# Orbiter_V3_2.net
KiCad netlist of a schematic drawn in EAGLE
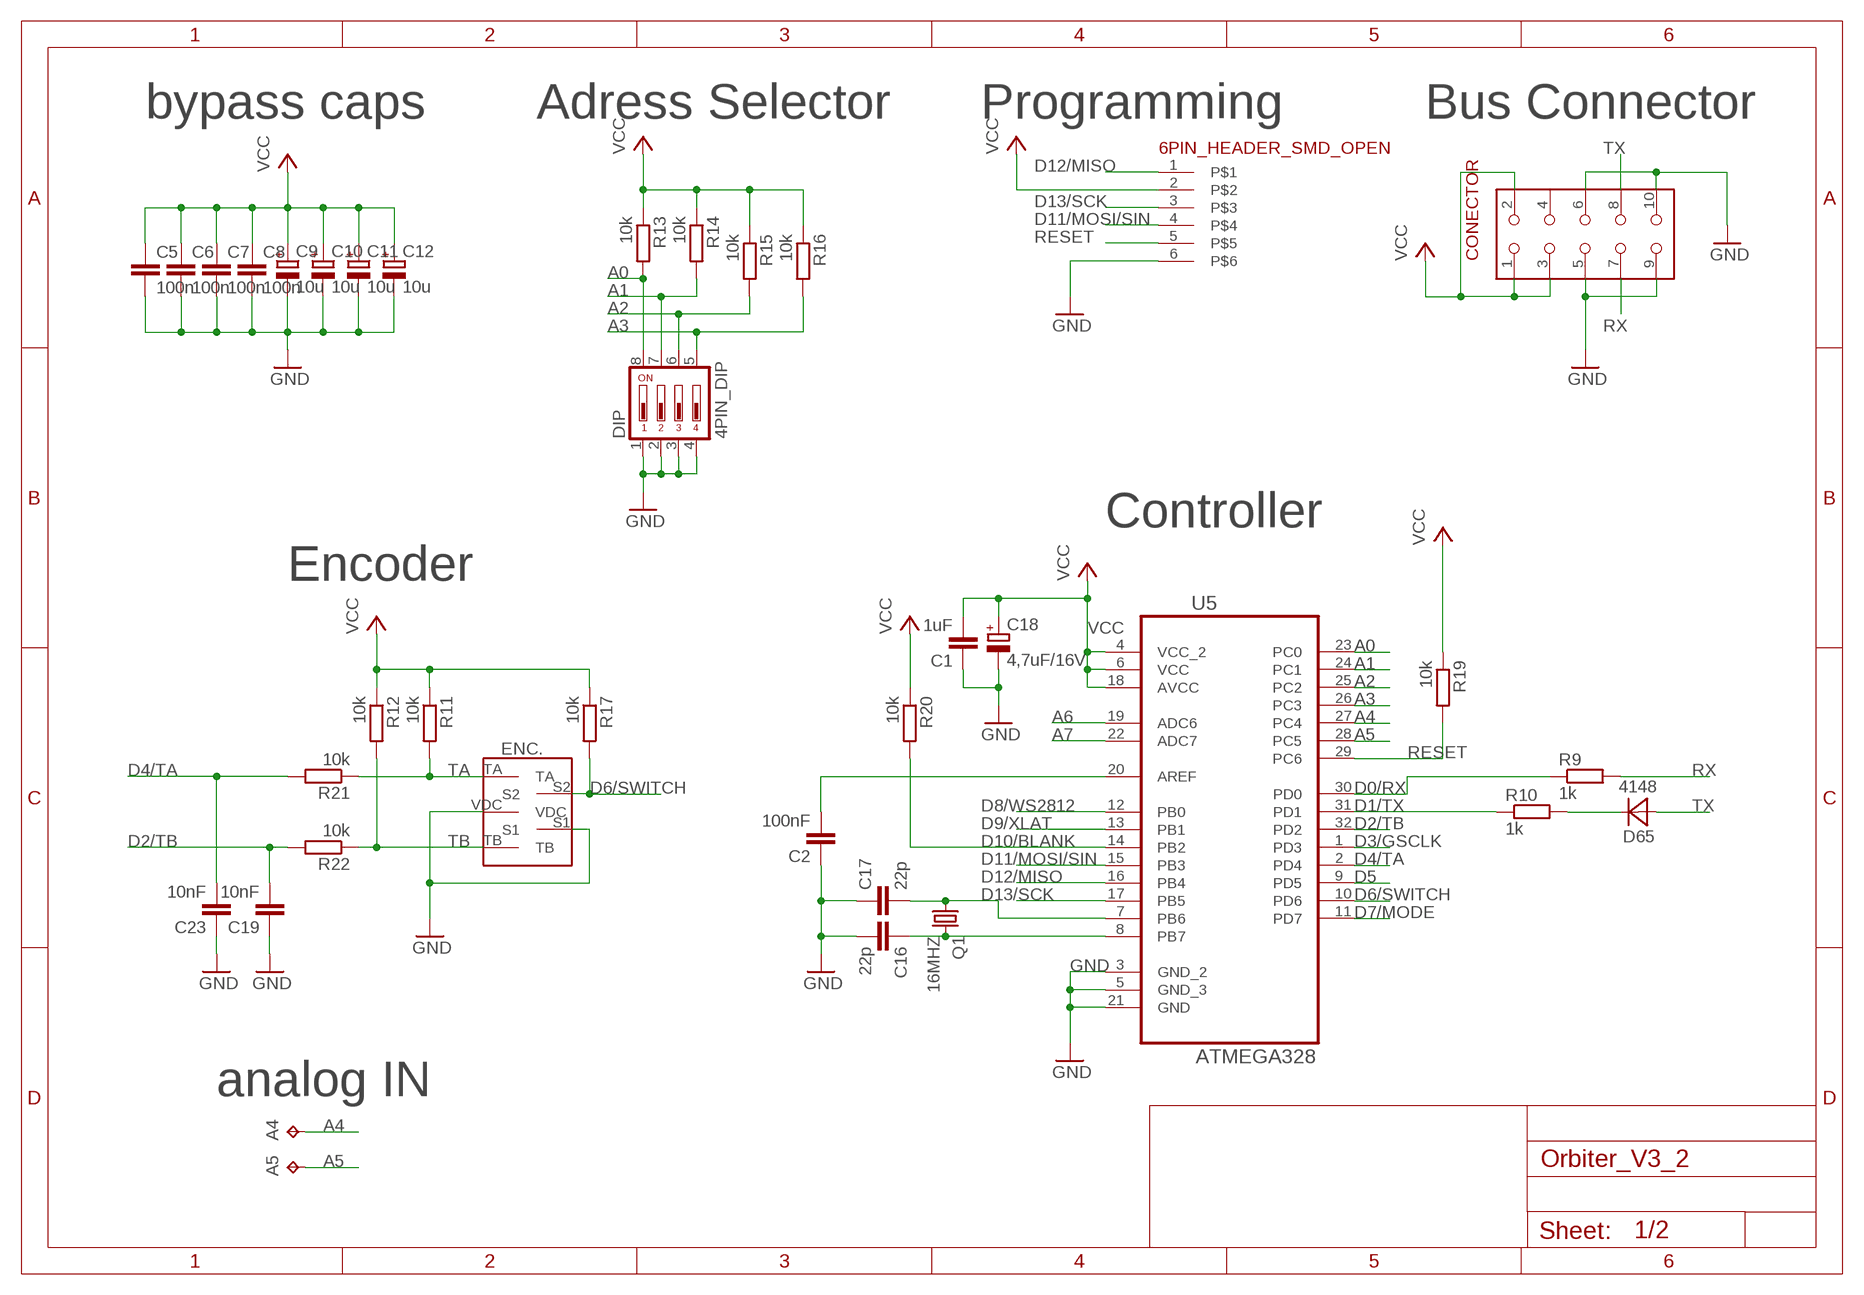
[diagram p0: schematic, sheet 1]
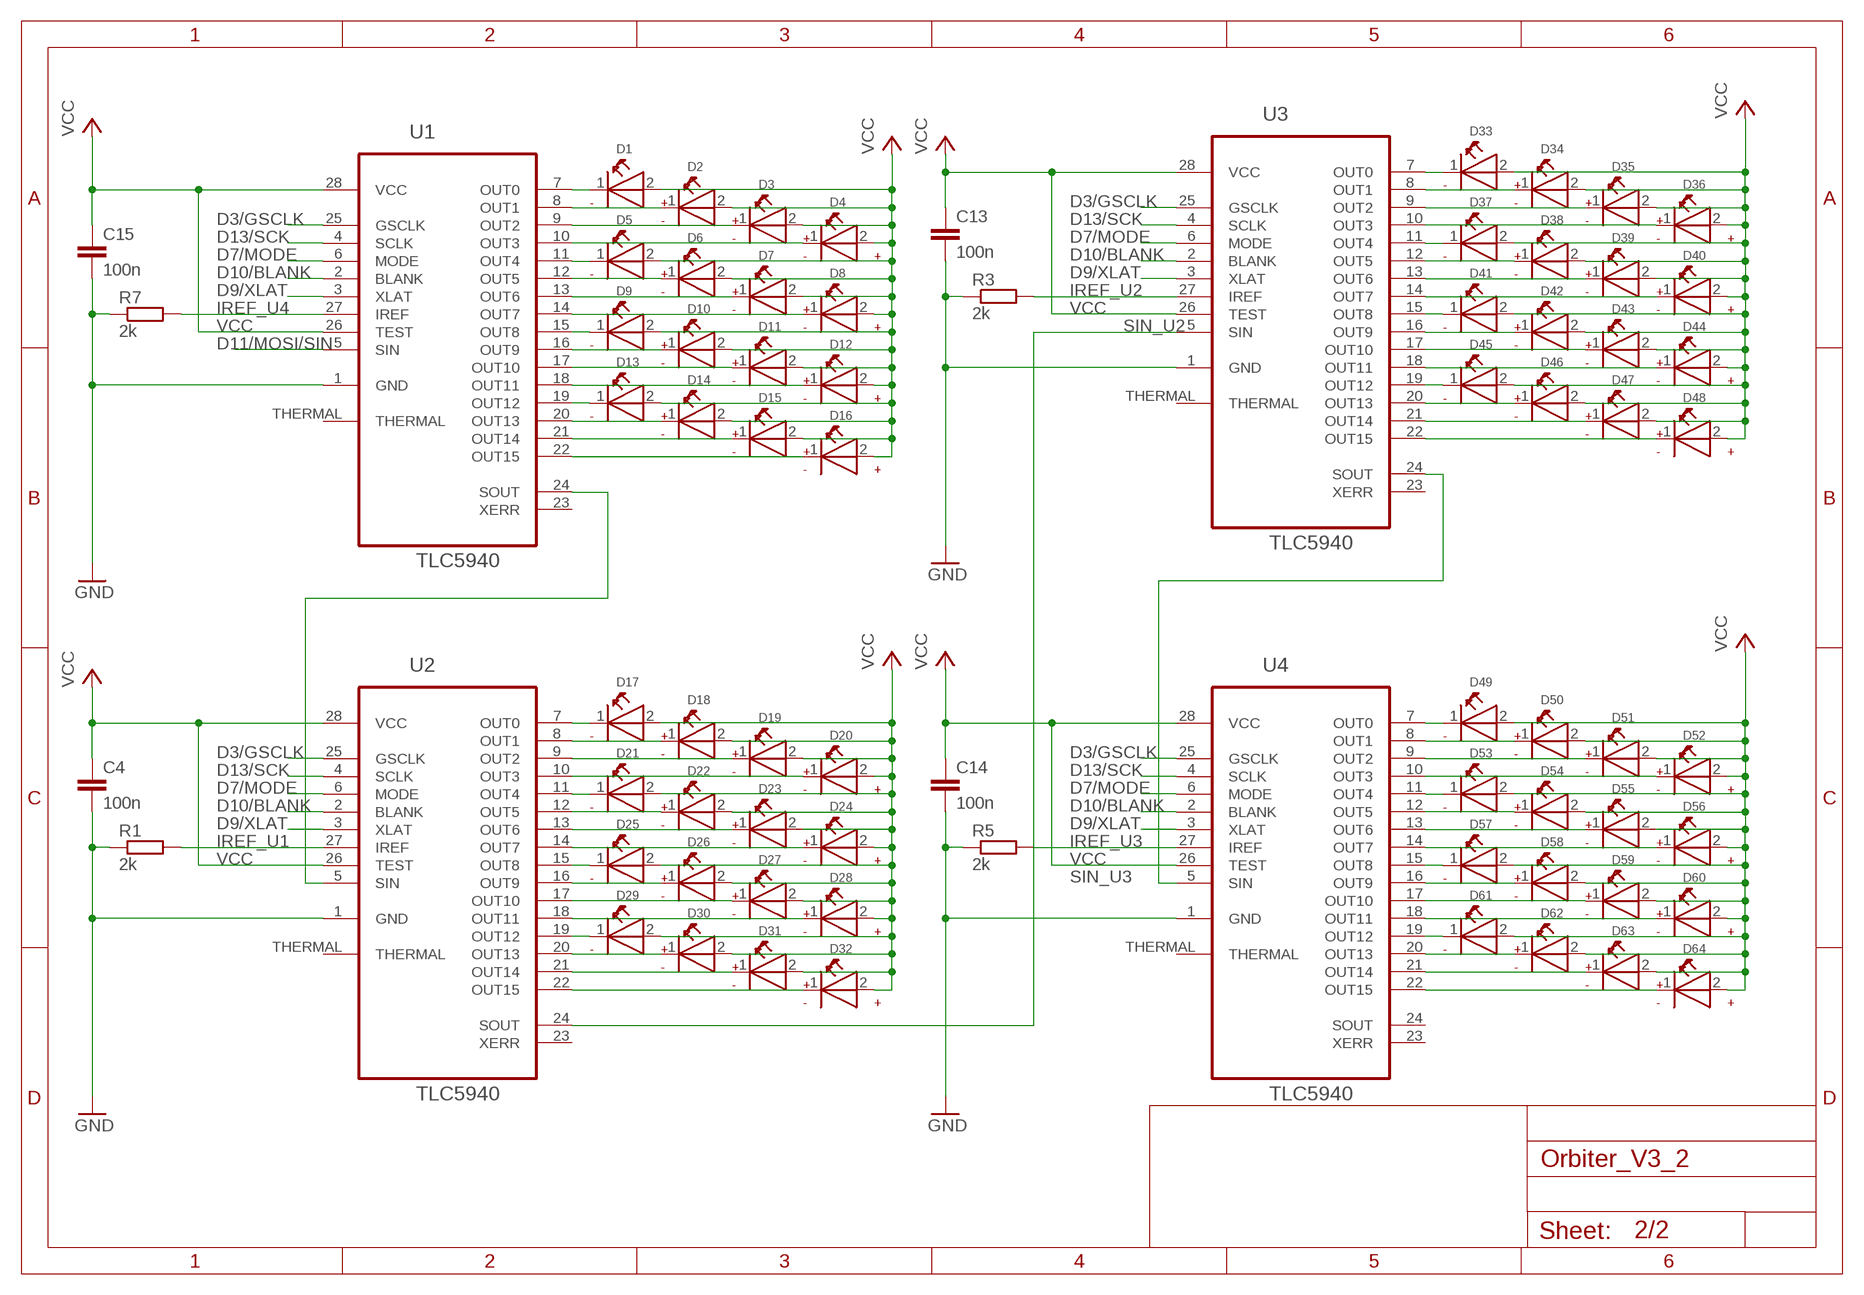
[diagram p1: schematic, sheet 2]

(export (version "E")
  (design (tool "Eeschema 10.0.6"))
  (components
    (comp (ref "A4")
      (value "TPSMD")
      (footprint "eagle-import:TP")
      (libsource (lib "eagle-import") (part "TPSMD"))
    )
    (comp (ref "A5")
      (value "TPSMD")
      (footprint "eagle-import:TP")
      (libsource (lib "eagle-import") (part "TPSMD"))
    )
    (comp (ref "C1")
      (value "1uF")
      (footprint "eagle-import:C0603")
      (libsource (lib "eagle-import") (part "CAPACITOR{dblquote}"))
    )
    (comp (ref "C2")
      (value "100nF")
      (footprint "eagle-import:C0603")
      (libsource (lib "eagle-import") (part "CAPACITOR{dblquote}"))
    )
    (comp (ref "C5")
      (value "100n")
      (footprint "eagle-import:C0603")
      (libsource (lib "eagle-import") (part "CAPACITOR{dblquote}"))
    )
    (comp (ref "C6")
      (value "100n")
      (footprint "eagle-import:C0603")
      (libsource (lib "eagle-import") (part "CAPACITOR{dblquote}"))
    )
    (comp (ref "C7")
      (value "100n")
      (footprint "eagle-import:C0603")
      (libsource (lib "eagle-import") (part "CAPACITOR{dblquote}"))
    )
    (comp (ref "C8")
      (value "100n")
      (footprint "eagle-import:C0603")
      (libsource (lib "eagle-import") (part "CAPACITOR{dblquote}"))
    )
    (comp (ref "C9")
      (value "10u")
      (footprint "eagle-import:153CLV-0605")
      (libsource (lib "eagle-import") (part "SMD_ELCTROLYTIC"))
    )
    (comp (ref "C10")
      (value "10u")
      (footprint "eagle-import:153CLV-0605")
      (libsource (lib "eagle-import") (part "SMD_ELCTROLYTIC"))
    )
    (comp (ref "C11")
      (value "10u")
      (footprint "eagle-import:153CLV-0605")
      (libsource (lib "eagle-import") (part "SMD_ELCTROLYTIC"))
    )
    (comp (ref "C12")
      (value "10u")
      (footprint "eagle-import:153CLV-0605")
      (libsource (lib "eagle-import") (part "SMD_ELCTROLYTIC"))
    )
    (comp (ref "C16")
      (value "22p")
      (footprint "eagle-import:C0603")
      (libsource (lib "eagle-import") (part "CAPACITOR{dblquote}"))
    )
    (comp (ref "C17")
      (value "22p")
      (footprint "eagle-import:C0603")
      (libsource (lib "eagle-import") (part "CAPACITOR{dblquote}"))
    )
    (comp (ref "C18")
      (value "4,7uF/16V")
      (footprint "eagle-import:153CLV-0605")
      (libsource (lib "eagle-import") (part "SMD_ELCTROLYTIC"))
    )
    (comp (ref "C19")
      (value "10nF")
      (footprint "eagle-import:C0603")
      (libsource (lib "eagle-import") (part "CAPACITOR{dblquote}"))
    )
    (comp (ref "C23")
      (value "10nF")
      (footprint "eagle-import:C0603")
      (libsource (lib "eagle-import") (part "CAPACITOR{dblquote}"))
    )
    (comp (ref "CONECTOR")
      (value "10PIN_HEADER_SMD")
      (footprint "eagle-import:87832-10")
      (libsource (lib "eagle-import") (part "10PIN_HEADER_SMD"))
    )
    (comp (ref "D65")
      (value "4148")
      (footprint "eagle-import:SOD323-R")
      (libsource (lib "eagle-import") (part "4148"))
    )
    (comp (ref "DIP")
      (value "4PIN_DIP")
      (footprint "eagle-import:CTS-219-04")
      (libsource (lib "eagle-import") (part "4PIN_DIP"))
    )
    (comp (ref "ENC.")
      (value "BOURNS_ENCODER")
      (footprint "eagle-import:BOURNS_ENCODER_SMD")
      (libsource (lib "eagle-import") (part "BOURNS_ENCODER"))
    )
    (comp (ref "PROG.")
      (value "6PIN_HEADER_SMD_OPEN")
      (footprint "eagle-import:6PIN_HEADER_SMD_OPEN")
      (libsource (lib "eagle-import") (part "6PIN_HEADER_SMD_OPEN"))
    )
    (comp (ref "Q1")
      (value "16MHZ")
      (footprint "eagle-import:SM49")
      (libsource (lib "eagle-import") (part "CRYSTAL_SM49"))
    )
    (comp (ref "R9")
      (value "1k")
      (footprint "eagle-import:R0805")
      (libsource (lib "eagle-import") (part "RESISTOR{dblquote}"))
    )
    (comp (ref "R10")
      (value "1k")
      (footprint "eagle-import:R0805")
      (libsource (lib "eagle-import") (part "RESISTOR{dblquote}"))
    )
    (comp (ref "R11")
      (value "10k")
      (footprint "eagle-import:R0805")
      (libsource (lib "eagle-import") (part "RESISTOR{dblquote}"))
    )
    (comp (ref "R12")
      (value "10k")
      (footprint "eagle-import:R0805")
      (libsource (lib "eagle-import") (part "RESISTOR{dblquote}"))
    )
    (comp (ref "R13")
      (value "10k")
      (footprint "eagle-import:R0805")
      (libsource (lib "eagle-import") (part "RESISTOR{dblquote}"))
    )
    (comp (ref "R14")
      (value "10k")
      (footprint "eagle-import:R0805")
      (libsource (lib "eagle-import") (part "RESISTOR{dblquote}"))
    )
    (comp (ref "R15")
      (value "10k")
      (footprint "eagle-import:R0805")
      (libsource (lib "eagle-import") (part "RESISTOR{dblquote}"))
    )
    (comp (ref "R16")
      (value "10k")
      (footprint "eagle-import:R0805")
      (libsource (lib "eagle-import") (part "RESISTOR{dblquote}"))
    )
    (comp (ref "R17")
      (value "10k")
      (footprint "eagle-import:R0805")
      (libsource (lib "eagle-import") (part "RESISTOR{dblquote}"))
    )
    (comp (ref "R19")
      (value "10k")
      (footprint "eagle-import:R0805")
      (libsource (lib "eagle-import") (part "RESISTOR{dblquote}"))
    )
    (comp (ref "R20")
      (value "10k")
      (footprint "eagle-import:R0805")
      (libsource (lib "eagle-import") (part "RESISTOR{dblquote}"))
    )
    (comp (ref "R21")
      (value "10k")
      (footprint "eagle-import:R0805")
      (libsource (lib "eagle-import") (part "RESISTOR{dblquote}"))
    )
    (comp (ref "R22")
      (value "10k")
      (footprint "eagle-import:R0805")
      (libsource (lib "eagle-import") (part "RESISTOR{dblquote}"))
    )
    (comp (ref "U5")
      (value "ATMEGA328")
      (footprint "eagle-import:QFP80P900X900X120-32N")
      (fields (field (name "MPN") "ATMEGA328P-AU"))
      (libsource (lib "eagle-import") (part "ATMEGA328P-AU"))
    )
    (comp (ref "C4")
      (value "100n")
      (footprint "eagle-import:C0603")
      (libsource (lib "eagle-import") (part "CAPACITOR{dblquote}"))
    )
    (comp (ref "C13")
      (value "100n")
      (footprint "eagle-import:C0603")
      (libsource (lib "eagle-import") (part "CAPACITOR{dblquote}"))
    )
    (comp (ref "C14")
      (value "100n")
      (footprint "eagle-import:C0603")
      (libsource (lib "eagle-import") (part "CAPACITOR{dblquote}"))
    )
    (comp (ref "C15")
      (value "100n")
      (footprint "eagle-import:C0603")
      (libsource (lib "eagle-import") (part "CAPACITOR{dblquote}"))
    )
    (comp (ref "D1")
      (value "SMD_LED_0603")
      (footprint "eagle-import:WL-SMCW_0603")
      (libsource (lib "eagle-import") (part "SMD_LED_0603"))
    )
    (comp (ref "D2")
      (value "SMD_LED_0603")
      (footprint "eagle-import:WL-SMCW_0603")
      (libsource (lib "eagle-import") (part "SMD_LED_0603"))
    )
    (comp (ref "D3")
      (value "SMD_LED_0603")
      (footprint "eagle-import:WL-SMCW_0603")
      (libsource (lib "eagle-import") (part "SMD_LED_0603"))
    )
    (comp (ref "D4")
      (value "SMD_LED_0603")
      (footprint "eagle-import:WL-SMCW_0603")
      (libsource (lib "eagle-import") (part "SMD_LED_0603"))
    )
    (comp (ref "D5")
      (value "SMD_LED_0603")
      (footprint "eagle-import:WL-SMCW_0603")
      (libsource (lib "eagle-import") (part "SMD_LED_0603"))
    )
    (comp (ref "D6")
      (value "SMD_LED_0603")
      (footprint "eagle-import:WL-SMCW_0603")
      (libsource (lib "eagle-import") (part "SMD_LED_0603"))
    )
    (comp (ref "D7")
      (value "SMD_LED_0603")
      (footprint "eagle-import:WL-SMCW_0603")
      (libsource (lib "eagle-import") (part "SMD_LED_0603"))
    )
    (comp (ref "D8")
      (value "SMD_LED_0603")
      (footprint "eagle-import:WL-SMCW_0603")
      (libsource (lib "eagle-import") (part "SMD_LED_0603"))
    )
    (comp (ref "D9")
      (value "SMD_LED_0603")
      (footprint "eagle-import:WL-SMCW_0603")
      (libsource (lib "eagle-import") (part "SMD_LED_0603"))
    )
    (comp (ref "D10")
      (value "SMD_LED_0603")
      (footprint "eagle-import:WL-SMCW_0603")
      (libsource (lib "eagle-import") (part "SMD_LED_0603"))
    )
    (comp (ref "D11")
      (value "SMD_LED_0603")
      (footprint "eagle-import:WL-SMCW_0603")
      (libsource (lib "eagle-import") (part "SMD_LED_0603"))
    )
    (comp (ref "D12")
      (value "SMD_LED_0603")
      (footprint "eagle-import:WL-SMCW_0603")
      (libsource (lib "eagle-import") (part "SMD_LED_0603"))
    )
    (comp (ref "D13")
      (value "SMD_LED_0603")
      (footprint "eagle-import:WL-SMCW_0603")
      (libsource (lib "eagle-import") (part "SMD_LED_0603"))
    )
    (comp (ref "D14")
      (value "SMD_LED_0603")
      (footprint "eagle-import:WL-SMCW_0603")
      (libsource (lib "eagle-import") (part "SMD_LED_0603"))
    )
    (comp (ref "D15")
      (value "SMD_LED_0603")
      (footprint "eagle-import:WL-SMCW_0603")
      (libsource (lib "eagle-import") (part "SMD_LED_0603"))
    )
    (comp (ref "D16")
      (value "SMD_LED_0603")
      (footprint "eagle-import:WL-SMCW_0603")
      (libsource (lib "eagle-import") (part "SMD_LED_0603"))
    )
    (comp (ref "D17")
      (value "SMD_LED_0603")
      (footprint "eagle-import:WL-SMCW_0603")
      (libsource (lib "eagle-import") (part "SMD_LED_0603"))
    )
    (comp (ref "D18")
      (value "SMD_LED_0603")
      (footprint "eagle-import:WL-SMCW_0603")
      (libsource (lib "eagle-import") (part "SMD_LED_0603"))
    )
    (comp (ref "D19")
      (value "SMD_LED_0603")
      (footprint "eagle-import:WL-SMCW_0603")
      (libsource (lib "eagle-import") (part "SMD_LED_0603"))
    )
    (comp (ref "D20")
      (value "SMD_LED_0603")
      (footprint "eagle-import:WL-SMCW_0603")
      (libsource (lib "eagle-import") (part "SMD_LED_0603"))
    )
    (comp (ref "D21")
      (value "SMD_LED_0603")
      (footprint "eagle-import:WL-SMCW_0603")
      (libsource (lib "eagle-import") (part "SMD_LED_0603"))
    )
    (comp (ref "D22")
      (value "SMD_LED_0603")
      (footprint "eagle-import:WL-SMCW_0603")
      (libsource (lib "eagle-import") (part "SMD_LED_0603"))
    )
    (comp (ref "D23")
      (value "SMD_LED_0603")
      (footprint "eagle-import:WL-SMCW_0603")
      (libsource (lib "eagle-import") (part "SMD_LED_0603"))
    )
    (comp (ref "D24")
      (value "SMD_LED_0603")
      (footprint "eagle-import:WL-SMCW_0603")
      (libsource (lib "eagle-import") (part "SMD_LED_0603"))
    )
    (comp (ref "D25")
      (value "SMD_LED_0603")
      (footprint "eagle-import:WL-SMCW_0603")
      (libsource (lib "eagle-import") (part "SMD_LED_0603"))
    )
    (comp (ref "D26")
      (value "SMD_LED_0603")
      (footprint "eagle-import:WL-SMCW_0603")
      (libsource (lib "eagle-import") (part "SMD_LED_0603"))
    )
    (comp (ref "D27")
      (value "SMD_LED_0603")
      (footprint "eagle-import:WL-SMCW_0603")
      (libsource (lib "eagle-import") (part "SMD_LED_0603"))
    )
    (comp (ref "D28")
      (value "SMD_LED_0603")
      (footprint "eagle-import:WL-SMCW_0603")
      (libsource (lib "eagle-import") (part "SMD_LED_0603"))
    )
    (comp (ref "D29")
      (value "SMD_LED_0603")
      (footprint "eagle-import:WL-SMCW_0603")
      (libsource (lib "eagle-import") (part "SMD_LED_0603"))
    )
    (comp (ref "D30")
      (value "SMD_LED_0603")
      (footprint "eagle-import:WL-SMCW_0603")
      (libsource (lib "eagle-import") (part "SMD_LED_0603"))
    )
    (comp (ref "D31")
      (value "SMD_LED_0603")
      (footprint "eagle-import:WL-SMCW_0603")
      (libsource (lib "eagle-import") (part "SMD_LED_0603"))
    )
    (comp (ref "D32")
      (value "SMD_LED_0603")
      (footprint "eagle-import:WL-SMCW_0603")
      (libsource (lib "eagle-import") (part "SMD_LED_0603"))
    )
    (comp (ref "D33")
      (value "SMD_LED_0603")
      (footprint "eagle-import:WL-SMCW_0603")
      (libsource (lib "eagle-import") (part "SMD_LED_0603"))
    )
    (comp (ref "D34")
      (value "SMD_LED_0603")
      (footprint "eagle-import:WL-SMCW_0603")
      (libsource (lib "eagle-import") (part "SMD_LED_0603"))
    )
    (comp (ref "D35")
      (value "SMD_LED_0603")
      (footprint "eagle-import:WL-SMCW_0603")
      (libsource (lib "eagle-import") (part "SMD_LED_0603"))
    )
    (comp (ref "D36")
      (value "SMD_LED_0603")
      (footprint "eagle-import:WL-SMCW_0603")
      (libsource (lib "eagle-import") (part "SMD_LED_0603"))
    )
    (comp (ref "D37")
      (value "SMD_LED_0603")
      (footprint "eagle-import:WL-SMCW_0603")
      (libsource (lib "eagle-import") (part "SMD_LED_0603"))
    )
    (comp (ref "D38")
      (value "SMD_LED_0603")
      (footprint "eagle-import:WL-SMCW_0603")
      (libsource (lib "eagle-import") (part "SMD_LED_0603"))
    )
    (comp (ref "D39")
      (value "SMD_LED_0603")
      (footprint "eagle-import:WL-SMCW_0603")
      (libsource (lib "eagle-import") (part "SMD_LED_0603"))
    )
    (comp (ref "D40")
      (value "SMD_LED_0603")
      (footprint "eagle-import:WL-SMCW_0603")
      (libsource (lib "eagle-import") (part "SMD_LED_0603"))
    )
    (comp (ref "D41")
      (value "SMD_LED_0603")
      (footprint "eagle-import:WL-SMCW_0603")
      (libsource (lib "eagle-import") (part "SMD_LED_0603"))
    )
    (comp (ref "D42")
      (value "SMD_LED_0603")
      (footprint "eagle-import:WL-SMCW_0603")
      (libsource (lib "eagle-import") (part "SMD_LED_0603"))
    )
    (comp (ref "D43")
      (value "SMD_LED_0603")
      (footprint "eagle-import:WL-SMCW_0603")
      (libsource (lib "eagle-import") (part "SMD_LED_0603"))
    )
    (comp (ref "D44")
      (value "SMD_LED_0603")
      (footprint "eagle-import:WL-SMCW_0603")
      (libsource (lib "eagle-import") (part "SMD_LED_0603"))
    )
    (comp (ref "D45")
      (value "SMD_LED_0603")
      (footprint "eagle-import:WL-SMCW_0603")
      (libsource (lib "eagle-import") (part "SMD_LED_0603"))
    )
    (comp (ref "D46")
      (value "SMD_LED_0603")
      (footprint "eagle-import:WL-SMCW_0603")
      (libsource (lib "eagle-import") (part "SMD_LED_0603"))
    )
    (comp (ref "D47")
      (value "SMD_LED_0603")
      (footprint "eagle-import:WL-SMCW_0603")
      (libsource (lib "eagle-import") (part "SMD_LED_0603"))
    )
    (comp (ref "D48")
      (value "SMD_LED_0603")
      (footprint "eagle-import:WL-SMCW_0603")
      (libsource (lib "eagle-import") (part "SMD_LED_0603"))
    )
    (comp (ref "D49")
      (value "SMD_LED_0603")
      (footprint "eagle-import:WL-SMCW_0603")
      (libsource (lib "eagle-import") (part "SMD_LED_0603"))
    )
    (comp (ref "D50")
      (value "SMD_LED_0603")
      (footprint "eagle-import:WL-SMCW_0603")
      (libsource (lib "eagle-import") (part "SMD_LED_0603"))
    )
    (comp (ref "D51")
      (value "SMD_LED_0603")
      (footprint "eagle-import:WL-SMCW_0603")
      (libsource (lib "eagle-import") (part "SMD_LED_0603"))
    )
    (comp (ref "D52")
      (value "SMD_LED_0603")
      (footprint "eagle-import:WL-SMCW_0603")
      (libsource (lib "eagle-import") (part "SMD_LED_0603"))
    )
    (comp (ref "D53")
      (value "SMD_LED_0603")
      (footprint "eagle-import:WL-SMCW_0603")
      (libsource (lib "eagle-import") (part "SMD_LED_0603"))
    )
    (comp (ref "D54")
      (value "SMD_LED_0603")
      (footprint "eagle-import:WL-SMCW_0603")
      (libsource (lib "eagle-import") (part "SMD_LED_0603"))
    )
    (comp (ref "D55")
      (value "SMD_LED_0603")
      (footprint "eagle-import:WL-SMCW_0603")
      (libsource (lib "eagle-import") (part "SMD_LED_0603"))
    )
    (comp (ref "D56")
      (value "SMD_LED_0603")
      (footprint "eagle-import:WL-SMCW_0603")
      (libsource (lib "eagle-import") (part "SMD_LED_0603"))
    )
    (comp (ref "D57")
      (value "SMD_LED_0603")
      (footprint "eagle-import:WL-SMCW_0603")
      (libsource (lib "eagle-import") (part "SMD_LED_0603"))
    )
    (comp (ref "D58")
      (value "SMD_LED_0603")
      (footprint "eagle-import:WL-SMCW_0603")
      (libsource (lib "eagle-import") (part "SMD_LED_0603"))
    )
    (comp (ref "D59")
      (value "SMD_LED_0603")
      (footprint "eagle-import:WL-SMCW_0603")
      (libsource (lib "eagle-import") (part "SMD_LED_0603"))
    )
    (comp (ref "D60")
      (value "SMD_LED_0603")
      (footprint "eagle-import:WL-SMCW_0603")
      (libsource (lib "eagle-import") (part "SMD_LED_0603"))
    )
    (comp (ref "D61")
      (value "SMD_LED_0603")
      (footprint "eagle-import:WL-SMCW_0603")
      (libsource (lib "eagle-import") (part "SMD_LED_0603"))
    )
    (comp (ref "D62")
      (value "SMD_LED_0603")
      (footprint "eagle-import:WL-SMCW_0603")
      (libsource (lib "eagle-import") (part "SMD_LED_0603"))
    )
    (comp (ref "D63")
      (value "SMD_LED_0603")
      (footprint "eagle-import:WL-SMCW_0603")
      (libsource (lib "eagle-import") (part "SMD_LED_0603"))
    )
    (comp (ref "D64")
      (value "SMD_LED_0603")
      (footprint "eagle-import:WL-SMCW_0603")
      (libsource (lib "eagle-import") (part "SMD_LED_0603"))
    )
    (comp (ref "R1")
      (value "2k")
      (footprint "eagle-import:R0805")
      (libsource (lib "eagle-import") (part "RESISTOR{dblquote}"))
    )
    (comp (ref "R3")
      (value "2k")
      (footprint "eagle-import:R0805")
      (libsource (lib "eagle-import") (part "RESISTOR{dblquote}"))
    )
    (comp (ref "R5")
      (value "2k")
      (footprint "eagle-import:R0805")
      (libsource (lib "eagle-import") (part "RESISTOR{dblquote}"))
    )
    (comp (ref "R7")
      (value "2k")
      (footprint "eagle-import:R0805")
      (libsource (lib "eagle-import") (part "RESISTOR{dblquote}"))
    )
    (comp (ref "U1")
      (value "TLC5940")
      (footprint "eagle-import:SOP65P640X120-29N")
      (fields (field (name "MPN") "TLC59401PWP"))
      (libsource (lib "eagle-import") (part "TLC59401PWP"))
    )
    (comp (ref "U2")
      (value "TLC5940")
      (footprint "eagle-import:SOP65P640X120-29N")
      (fields (field (name "MPN") "TLC59401PWP"))
      (libsource (lib "eagle-import") (part "TLC59401PWP"))
    )
    (comp (ref "U3")
      (value "TLC5940")
      (footprint "eagle-import:SOP65P640X120-29N")
      (fields (field (name "MPN") "TLC59401PWP"))
      (libsource (lib "eagle-import") (part "TLC59401PWP"))
    )
    (comp (ref "U4")
      (value "TLC5940")
      (footprint "eagle-import:SOP65P640X120-29N")
      (fields (field (name "MPN") "TLC59401PWP"))
      (libsource (lib "eagle-import") (part "TLC59401PWP"))
    )
  )
  (nets
    (net (code "1") (name "A0") (class "Default")
      (node (ref "DIP") (pin "8") (pinfunction "8_8") (pintype "passive"))
      (node (ref "R13") (pin "2") (pinfunction "2_2") (pintype "passive"))
      (node (ref "U5") (pin "23") (pinfunction "PC0_23") (pintype "bidirectional"))
    )
    (net (code "2") (name "A1") (class "Default")
      (node (ref "DIP") (pin "7") (pinfunction "7_7") (pintype "passive"))
      (node (ref "R14") (pin "2") (pinfunction "2_2") (pintype "passive"))
      (node (ref "U5") (pin "24") (pinfunction "PC1_24") (pintype "bidirectional"))
    )
    (net (code "3") (name "A2") (class "Default")
      (node (ref "DIP") (pin "6") (pinfunction "6_6") (pintype "passive"))
      (node (ref "R15") (pin "2") (pinfunction "2_2") (pintype "passive"))
      (node (ref "U5") (pin "25") (pinfunction "PC2_25") (pintype "bidirectional"))
    )
    (net (code "4") (name "A3") (class "Default")
      (node (ref "DIP") (pin "5") (pinfunction "5_5") (pintype "passive"))
      (node (ref "R16") (pin "2") (pinfunction "2_2") (pintype "passive"))
      (node (ref "U5") (pin "26") (pinfunction "PC3_26") (pintype "bidirectional"))
    )
    (net (code "5") (name "A4") (class "Default")
      (node (ref "A4") (pin "P$1") (pinfunction "TP_P$1") (pintype "input"))
      (node (ref "U5") (pin "27") (pinfunction "PC4_27") (pintype "bidirectional"))
    )
    (net (code "6") (name "A5") (class "Default")
      (node (ref "A5") (pin "P$1") (pinfunction "TP_P$1") (pintype "input"))
      (node (ref "U5") (pin "28") (pinfunction "PC5_28") (pintype "bidirectional"))
    )
    (net (code "7") (name "A6") (class "Default")
      (node (ref "U5") (pin "19") (pinfunction "ADC6_19") (pintype "input"))
    )
    (net (code "8") (name "A7") (class "Default")
      (node (ref "U5") (pin "22") (pinfunction "ADC7_22") (pintype "input"))
    )
    (net (code "9") (name "D0{slash}RX") (class "Default")
      (node (ref "R9") (pin "1") (pinfunction "1_1") (pintype "passive"))
      (node (ref "U5") (pin "30") (pinfunction "PD0_30") (pintype "bidirectional"))
    )
    (net (code "10") (name "D1{slash}TX") (class "Default")
      (node (ref "R10") (pin "1") (pinfunction "1_1") (pintype "passive"))
      (node (ref "U5") (pin "31") (pinfunction "PD1_31") (pintype "bidirectional"))
    )
    (net (code "11") (name "D2{slash}TB") (class "Default")
      (node (ref "C19") (pin "2") (pinfunction "2_2") (pintype "passive"))
      (node (ref "R22") (pin "2") (pinfunction "2_2") (pintype "passive"))
      (node (ref "U5") (pin "32") (pinfunction "PD2_32") (pintype "bidirectional"))
    )
    (net (code "12") (name "D3{slash}GSCLK") (class "Default")
      (node (ref "U1") (pin "25") (pinfunction "GSCLK_25") (pintype "input"))
      (node (ref "U2") (pin "25") (pinfunction "GSCLK_25") (pintype "input"))
      (node (ref "U3") (pin "25") (pinfunction "GSCLK_25") (pintype "input"))
      (node (ref "U4") (pin "25") (pinfunction "GSCLK_25") (pintype "input"))
      (node (ref "U5") (pin "1") (pinfunction "PD3_1") (pintype "bidirectional"))
    )
    (net (code "13") (name "D4{slash}TA") (class "Default")
      (node (ref "C23") (pin "2") (pinfunction "2_2") (pintype "passive"))
      (node (ref "R21") (pin "2") (pinfunction "2_2") (pintype "passive"))
      (node (ref "U5") (pin "2") (pinfunction "PD4_2") (pintype "bidirectional"))
    )
    (net (code "14") (name "D5") (class "Default")
      (node (ref "U5") (pin "9") (pinfunction "PD5_9") (pintype "bidirectional"))
    )
    (net (code "15") (name "D6{slash}SWITCH") (class "Default")
      (node (ref "ENC.") (pin "S2") (pinfunction "S2_S2") (pintype "bidirectional"))
      (node (ref "R17") (pin "2") (pinfunction "2_2") (pintype "passive"))
      (node (ref "U5") (pin "10") (pinfunction "PD6_10") (pintype "bidirectional"))
    )
    (net (code "16") (name "D7{slash}MODE") (class "Default")
      (node (ref "U1") (pin "6") (pinfunction "MODE_6") (pintype "input"))
      (node (ref "U2") (pin "6") (pinfunction "MODE_6") (pintype "input"))
      (node (ref "U3") (pin "6") (pinfunction "MODE_6") (pintype "input"))
      (node (ref "U4") (pin "6") (pinfunction "MODE_6") (pintype "input"))
      (node (ref "U5") (pin "11") (pinfunction "PD7_11") (pintype "bidirectional"))
    )
    (net (code "17") (name "D8{slash}WS2812") (class "Default")
      (node (ref "U5") (pin "12") (pinfunction "PB0_12") (pintype "bidirectional"))
    )
    (net (code "18") (name "D9{slash}XLAT") (class "Default")
      (node (ref "U1") (pin "3") (pinfunction "XLAT_3") (pintype "input"))
      (node (ref "U2") (pin "3") (pinfunction "XLAT_3") (pintype "input"))
      (node (ref "U3") (pin "3") (pinfunction "XLAT_3") (pintype "input"))
      (node (ref "U4") (pin "3") (pinfunction "XLAT_3") (pintype "input"))
      (node (ref "U5") (pin "13") (pinfunction "PB1_13") (pintype "bidirectional"))
    )
    (net (code "19") (name "D10{slash}BLANK") (class "Default")
      (node (ref "R20") (pin "2") (pinfunction "2_2") (pintype "passive"))
      (node (ref "U1") (pin "2") (pinfunction "BLANK_2") (pintype "input"))
      (node (ref "U2") (pin "2") (pinfunction "BLANK_2") (pintype "input"))
      (node (ref "U3") (pin "2") (pinfunction "BLANK_2") (pintype "input"))
      (node (ref "U4") (pin "2") (pinfunction "BLANK_2") (pintype "input"))
      (node (ref "U5") (pin "14") (pinfunction "PB2_14") (pintype "bidirectional"))
    )
    (net (code "20") (name "D11{slash}MOSI{slash}SIN") (class "Default")
      (node (ref "PROG.") (pin "4") (pinfunction "P$4_4") (pintype "bidirectional"))
      (node (ref "U1") (pin "5") (pinfunction "SIN_5") (pintype "input"))
      (node (ref "U5") (pin "15") (pinfunction "PB3_15") (pintype "bidirectional"))
    )
    (net (code "21") (name "D12{slash}MISO") (class "Default")
      (node (ref "PROG.") (pin "1") (pinfunction "P$1_1") (pintype "bidirectional"))
      (node (ref "U5") (pin "16") (pinfunction "PB4_16") (pintype "bidirectional"))
    )
    (net (code "22") (name "D13{slash}SCK") (class "Default")
      (node (ref "PROG.") (pin "3") (pinfunction "P$3_3") (pintype "bidirectional"))
      (node (ref "U1") (pin "4") (pinfunction "SCLK_4") (pintype "input"))
      (node (ref "U2") (pin "4") (pinfunction "SCLK_4") (pintype "input"))
      (node (ref "U3") (pin "4") (pinfunction "SCLK_4") (pintype "input"))
      (node (ref "U4") (pin "4") (pinfunction "SCLK_4") (pintype "input"))
      (node (ref "U5") (pin "17") (pinfunction "PB5_17") (pintype "bidirectional"))
    )
    (net (code "23") (name "GND") (class "Default")
      (node (ref "C1") (pin "1") (pinfunction "1_1") (pintype "passive"))
      (node (ref "C10") (pin "-") (pinfunction "-_-") (pintype "passive"))
      (node (ref "C11") (pin "-") (pinfunction "-_-") (pintype "passive"))
      (node (ref "C12") (pin "-") (pinfunction "-_-") (pintype "passive"))
      (node (ref "C13") (pin "2") (pinfunction "2_2") (pintype "passive"))
      (node (ref "C14") (pin "2") (pinfunction "2_2") (pintype "passive"))
      (node (ref "C15") (pin "2") (pinfunction "2_2") (pintype "passive"))
      (node (ref "C16") (pin "2") (pinfunction "2_2") (pintype "passive"))
      (node (ref "C17") (pin "1") (pinfunction "1_1") (pintype "passive"))
      (node (ref "C18") (pin "-") (pinfunction "-_-") (pintype "passive"))
      (node (ref "C19") (pin "1") (pinfunction "1_1") (pintype "passive"))
      (node (ref "C2") (pin "1") (pinfunction "1_1") (pintype "passive"))
      (node (ref "C23") (pin "1") (pinfunction "1_1") (pintype "passive"))
      (node (ref "C4") (pin "2") (pinfunction "2_2") (pintype "passive"))
      (node (ref "C5") (pin "2") (pinfunction "2_2") (pintype "passive"))
      (node (ref "C6") (pin "2") (pinfunction "2_2") (pintype "passive"))
      (node (ref "C7") (pin "2") (pinfunction "2_2") (pintype "passive"))
      (node (ref "C8") (pin "2") (pinfunction "2_2") (pintype "passive"))
      (node (ref "C9") (pin "-") (pinfunction "-_-") (pintype "passive"))
      (node (ref "CONECTOR") (pin "10") (pinfunction "P$10_10") (pintype "bidirectional"))
      (node (ref "CONECTOR") (pin "5") (pinfunction "P$5_5") (pintype "bidirectional"))
      (node (ref "CONECTOR") (pin "6") (pinfunction "P$6_6") (pintype "bidirectional"))
      (node (ref "CONECTOR") (pin "9") (pinfunction "P$9_9") (pintype "bidirectional"))
      (node (ref "DIP") (pin "1") (pinfunction "1_1") (pintype "passive"))
      (node (ref "DIP") (pin "2") (pinfunction "2_2") (pintype "passive"))
      (node (ref "DIP") (pin "3") (pinfunction "3_3") (pintype "passive"))
      (node (ref "DIP") (pin "4") (pinfunction "4_4") (pintype "passive"))
      (node (ref "ENC.") (pin "S1") (pinfunction "S1_S1") (pintype "bidirectional"))
      (node (ref "ENC.") (pin "VDC") (pinfunction "VDC_VDC") (pintype "bidirectional"))
      (node (ref "PROG.") (pin "6") (pinfunction "P$6_6") (pintype "bidirectional"))
      (node (ref "R1") (pin "1") (pinfunction "1_1") (pintype "passive"))
      (node (ref "R3") (pin "1") (pinfunction "1_1") (pintype "passive"))
      (node (ref "R5") (pin "1") (pinfunction "1_1") (pintype "passive"))
      (node (ref "R7") (pin "1") (pinfunction "1_1") (pintype "passive"))
      (node (ref "U1") (pin "1") (pinfunction "GND_1") (pintype "passive"))
      (node (ref "U2") (pin "1") (pinfunction "GND_1") (pintype "passive"))
      (node (ref "U3") (pin "1") (pinfunction "GND_1") (pintype "passive"))
      (node (ref "U4") (pin "1") (pinfunction "GND_1") (pintype "passive"))
      (node (ref "U5") (pin "21") (pinfunction "GND_21") (pintype "passive"))
      (node (ref "U5") (pin "3") (pinfunction "GND_2_3") (pintype "passive"))
      (node (ref "U5") (pin "5") (pinfunction "GND_3_5") (pintype "passive"))
    )
    (net (code "24") (name "IREF_U1") (class "Default")
      (node (ref "R1") (pin "2") (pinfunction "2_2") (pintype "passive"))
      (node (ref "U2") (pin "27") (pinfunction "IREF_27") (pintype "input"))
    )
    (net (code "25") (name "IREF_U2") (class "Default")
      (node (ref "R3") (pin "2") (pinfunction "2_2") (pintype "passive"))
      (node (ref "U3") (pin "27") (pinfunction "IREF_27") (pintype "input"))
    )
    (net (code "26") (name "IREF_U3") (class "Default")
      (node (ref "R5") (pin "2") (pinfunction "2_2") (pintype "passive"))
      (node (ref "U4") (pin "27") (pinfunction "IREF_27") (pintype "input"))
    )
    (net (code "27") (name "IREF_U4") (class "Default")
      (node (ref "R7") (pin "2") (pinfunction "2_2") (pintype "passive"))
      (node (ref "U1") (pin "27") (pinfunction "IREF_27") (pintype "input"))
    )
    (net (code "28") (name "Net-(D1--)") (class "Default")
      (node (ref "D1") (pin "1") (pinfunction "-_1") (pintype "passive"))
      (node (ref "U1") (pin "7") (pinfunction "OUT0_7") (pintype "output"))
    )
    (net (code "29") (name "Net-(D2--)") (class "Default")
      (node (ref "D2") (pin "1") (pinfunction "-_1") (pintype "passive"))
      (node (ref "U1") (pin "8") (pinfunction "OUT1_8") (pintype "output"))
    )
    (net (code "30") (name "Net-(D3--)") (class "Default")
      (node (ref "D3") (pin "1") (pinfunction "-_1") (pintype "passive"))
      (node (ref "U1") (pin "9") (pinfunction "OUT2_9") (pintype "output"))
    )
    (net (code "31") (name "Net-(D4--)") (class "Default")
      (node (ref "D4") (pin "1") (pinfunction "-_1") (pintype "passive"))
      (node (ref "U1") (pin "10") (pinfunction "OUT3_10") (pintype "output"))
    )
    (net (code "32") (name "Net-(D5--)") (class "Default")
      (node (ref "D5") (pin "1") (pinfunction "-_1") (pintype "passive"))
      (node (ref "U1") (pin "11") (pinfunction "OUT4_11") (pintype "output"))
    )
    (net (code "33") (name "Net-(D6--)") (class "Default")
      (node (ref "D6") (pin "1") (pinfunction "-_1") (pintype "passive"))
      (node (ref "U1") (pin "12") (pinfunction "OUT5_12") (pintype "output"))
    )
    (net (code "34") (name "Net-(D7--)") (class "Default")
      (node (ref "D7") (pin "1") (pinfunction "-_1") (pintype "passive"))
      (node (ref "U1") (pin "13") (pinfunction "OUT6_13") (pintype "output"))
    )
    (net (code "35") (name "Net-(D8--)") (class "Default")
      (node (ref "D8") (pin "1") (pinfunction "-_1") (pintype "passive"))
      (node (ref "U1") (pin "14") (pinfunction "OUT7_14") (pintype "output"))
    )
    (net (code "36") (name "Net-(D9--)") (class "Default")
      (node (ref "D9") (pin "1") (pinfunction "-_1") (pintype "passive"))
      (node (ref "U1") (pin "15") (pinfunction "OUT8_15") (pintype "output"))
    )
    (net (code "37") (name "Net-(D10--)") (class "Default")
      (node (ref "D10") (pin "1") (pinfunction "-_1") (pintype "passive"))
      (node (ref "U1") (pin "16") (pinfunction "OUT9_16") (pintype "output"))
    )
    (net (code "38") (name "Net-(D11--)") (class "Default")
      (node (ref "D11") (pin "1") (pinfunction "-_1") (pintype "passive"))
      (node (ref "U1") (pin "17") (pinfunction "OUT10_17") (pintype "output"))
    )
    (net (code "39") (name "Net-(D12--)") (class "Default")
      (node (ref "D12") (pin "1") (pinfunction "-_1") (pintype "passive"))
      (node (ref "U1") (pin "18") (pinfunction "OUT11_18") (pintype "output"))
    )
    (net (code "40") (name "Net-(D13--)") (class "Default")
      (node (ref "D13") (pin "1") (pinfunction "-_1") (pintype "passive"))
      (node (ref "U1") (pin "19") (pinfunction "OUT12_19") (pintype "output"))
    )
    (net (code "41") (name "Net-(D14--)") (class "Default")
      (node (ref "D14") (pin "1") (pinfunction "-_1") (pintype "passive"))
      (node (ref "U1") (pin "20") (pinfunction "OUT13_20") (pintype "output"))
    )
    (net (code "42") (name "Net-(D15--)") (class "Default")
      (node (ref "D15") (pin "1") (pinfunction "-_1") (pintype "passive"))
      (node (ref "U1") (pin "21") (pinfunction "OUT14_21") (pintype "output"))
    )
    (net (code "43") (name "Net-(D16--)") (class "Default")
      (node (ref "D16") (pin "1") (pinfunction "-_1") (pintype "passive"))
      (node (ref "U1") (pin "22") (pinfunction "OUT15_22") (pintype "output"))
    )
    (net (code "44") (name "Net-(D17--)") (class "Default")
      (node (ref "D17") (pin "1") (pinfunction "-_1") (pintype "passive"))
      (node (ref "U2") (pin "7") (pinfunction "OUT0_7") (pintype "output"))
    )
    (net (code "45") (name "Net-(D18--)") (class "Default")
      (node (ref "D18") (pin "1") (pinfunction "-_1") (pintype "passive"))
      (node (ref "U2") (pin "8") (pinfunction "OUT1_8") (pintype "output"))
    )
    (net (code "46") (name "Net-(D19--)") (class "Default")
      (node (ref "D19") (pin "1") (pinfunction "-_1") (pintype "passive"))
      (node (ref "U2") (pin "9") (pinfunction "OUT2_9") (pintype "output"))
    )
    (net (code "47") (name "Net-(D20--)") (class "Default")
      (node (ref "D20") (pin "1") (pinfunction "-_1") (pintype "passive"))
      (node (ref "U2") (pin "10") (pinfunction "OUT3_10") (pintype "output"))
    )
    (net (code "48") (name "Net-(D21--)") (class "Default")
      (node (ref "D21") (pin "1") (pinfunction "-_1") (pintype "passive"))
      (node (ref "U2") (pin "11") (pinfunction "OUT4_11") (pintype "output"))
    )
    (net (code "49") (name "Net-(D22--)") (class "Default")
      (node (ref "D22") (pin "1") (pinfunction "-_1") (pintype "passive"))
      (node (ref "U2") (pin "12") (pinfunction "OUT5_12") (pintype "output"))
    )
    (net (code "50") (name "Net-(D23--)") (class "Default")
      (node (ref "D23") (pin "1") (pinfunction "-_1") (pintype "passive"))
      (node (ref "U2") (pin "13") (pinfunction "OUT6_13") (pintype "output"))
    )
    (net (code "51") (name "Net-(D24--)") (class "Default")
      (node (ref "D24") (pin "1") (pinfunction "-_1") (pintype "passive"))
      (node (ref "U2") (pin "14") (pinfunction "OUT7_14") (pintype "output"))
    )
    (net (code "52") (name "Net-(D25--)") (class "Default")
      (node (ref "D25") (pin "1") (pinfunction "-_1") (pintype "passive"))
      (node (ref "U2") (pin "15") (pinfunction "OUT8_15") (pintype "output"))
    )
    (net (code "53") (name "Net-(D26--)") (class "Default")
      (node (ref "D26") (pin "1") (pinfunction "-_1") (pintype "passive"))
      (node (ref "U2") (pin "16") (pinfunction "OUT9_16") (pintype "output"))
    )
    (net (code "54") (name "Net-(D27--)") (class "Default")
      (node (ref "D27") (pin "1") (pinfunction "-_1") (pintype "passive"))
      (node (ref "U2") (pin "17") (pinfunction "OUT10_17") (pintype "output"))
    )
    (net (code "55") (name "Net-(D28--)") (class "Default")
      (node (ref "D28") (pin "1") (pinfunction "-_1") (pintype "passive"))
      (node (ref "U2") (pin "18") (pinfunction "OUT11_18") (pintype "output"))
    )
    (net (code "56") (name "Net-(D29--)") (class "Default")
      (node (ref "D29") (pin "1") (pinfunction "-_1") (pintype "passive"))
      (node (ref "U2") (pin "19") (pinfunction "OUT12_19") (pintype "output"))
    )
    (net (code "57") (name "Net-(D30--)") (class "Default")
      (node (ref "D30") (pin "1") (pinfunction "-_1") (pintype "passive"))
      (node (ref "U2") (pin "20") (pinfunction "OUT13_20") (pintype "output"))
    )
    (net (code "58") (name "Net-(D31--)") (class "Default")
      (node (ref "D31") (pin "1") (pinfunction "-_1") (pintype "passive"))
      (node (ref "U2") (pin "21") (pinfunction "OUT14_21") (pintype "output"))
    )
    (net (code "59") (name "Net-(D32--)") (class "Default")
      (node (ref "D32") (pin "1") (pinfunction "-_1") (pintype "passive"))
      (node (ref "U2") (pin "22") (pinfunction "OUT15_22") (pintype "output"))
    )
    (net (code "60") (name "Net-(D33--)") (class "Default")
      (node (ref "D33") (pin "1") (pinfunction "-_1") (pintype "passive"))
      (node (ref "U3") (pin "7") (pinfunction "OUT0_7") (pintype "output"))
    )
    (net (code "61") (name "Net-(D34--)") (class "Default")
      (node (ref "D34") (pin "1") (pinfunction "-_1") (pintype "passive"))
      (node (ref "U3") (pin "8") (pinfunction "OUT1_8") (pintype "output"))
    )
    (net (code "62") (name "Net-(D35--)") (class "Default")
      (node (ref "D35") (pin "1") (pinfunction "-_1") (pintype "passive"))
      (node (ref "U3") (pin "9") (pinfunction "OUT2_9") (pintype "output"))
    )
    (net (code "63") (name "Net-(D36--)") (class "Default")
      (node (ref "D36") (pin "1") (pinfunction "-_1") (pintype "passive"))
      (node (ref "U3") (pin "10") (pinfunction "OUT3_10") (pintype "output"))
    )
    (net (code "64") (name "Net-(D37--)") (class "Default")
      (node (ref "D37") (pin "1") (pinfunction "-_1") (pintype "passive"))
      (node (ref "U3") (pin "11") (pinfunction "OUT4_11") (pintype "output"))
    )
    (net (code "65") (name "Net-(D38--)") (class "Default")
      (node (ref "D38") (pin "1") (pinfunction "-_1") (pintype "passive"))
      (node (ref "U3") (pin "12") (pinfunction "OUT5_12") (pintype "output"))
    )
    (net (code "66") (name "Net-(D39--)") (class "Default")
      (node (ref "D39") (pin "1") (pinfunction "-_1") (pintype "passive"))
      (node (ref "U3") (pin "13") (pinfunction "OUT6_13") (pintype "output"))
    )
    (net (code "67") (name "Net-(D40--)") (class "Default")
      (node (ref "D40") (pin "1") (pinfunction "-_1") (pintype "passive"))
      (node (ref "U3") (pin "14") (pinfunction "OUT7_14") (pintype "output"))
    )
    (net (code "68") (name "Net-(D41--)") (class "Default")
      (node (ref "D41") (pin "1") (pinfunction "-_1") (pintype "passive"))
      (node (ref "U3") (pin "15") (pinfunction "OUT8_15") (pintype "output"))
    )
    (net (code "69") (name "Net-(D42--)") (class "Default")
      (node (ref "D42") (pin "1") (pinfunction "-_1") (pintype "passive"))
      (node (ref "U3") (pin "16") (pinfunction "OUT9_16") (pintype "output"))
    )
    (net (code "70") (name "Net-(D43--)") (class "Default")
      (node (ref "D43") (pin "1") (pinfunction "-_1") (pintype "passive"))
      (node (ref "U3") (pin "17") (pinfunction "OUT10_17") (pintype "output"))
    )
    (net (code "71") (name "Net-(D44--)") (class "Default")
      (node (ref "D44") (pin "1") (pinfunction "-_1") (pintype "passive"))
      (node (ref "U3") (pin "18") (pinfunction "OUT11_18") (pintype "output"))
    )
    (net (code "72") (name "Net-(D45--)") (class "Default")
      (node (ref "D45") (pin "1") (pinfunction "-_1") (pintype "passive"))
      (node (ref "U3") (pin "19") (pinfunction "OUT12_19") (pintype "output"))
    )
    (net (code "73") (name "Net-(D46--)") (class "Default")
      (node (ref "D46") (pin "1") (pinfunction "-_1") (pintype "passive"))
      (node (ref "U3") (pin "20") (pinfunction "OUT13_20") (pintype "output"))
    )
    (net (code "74") (name "Net-(D47--)") (class "Default")
      (node (ref "D47") (pin "1") (pinfunction "-_1") (pintype "passive"))
      (node (ref "U3") (pin "21") (pinfunction "OUT14_21") (pintype "output"))
    )
    (net (code "75") (name "Net-(D48--)") (class "Default")
      (node (ref "D48") (pin "1") (pinfunction "-_1") (pintype "passive"))
      (node (ref "U3") (pin "22") (pinfunction "OUT15_22") (pintype "output"))
    )
    (net (code "76") (name "Net-(D49--)") (class "Default")
      (node (ref "D49") (pin "1") (pinfunction "-_1") (pintype "passive"))
      (node (ref "U4") (pin "7") (pinfunction "OUT0_7") (pintype "output"))
    )
    (net (code "77") (name "Net-(D50--)") (class "Default")
      (node (ref "D50") (pin "1") (pinfunction "-_1") (pintype "passive"))
      (node (ref "U4") (pin "8") (pinfunction "OUT1_8") (pintype "output"))
    )
    (net (code "78") (name "Net-(D51--)") (class "Default")
      (node (ref "D51") (pin "1") (pinfunction "-_1") (pintype "passive"))
      (node (ref "U4") (pin "9") (pinfunction "OUT2_9") (pintype "output"))
    )
    (net (code "79") (name "Net-(D52--)") (class "Default")
      (node (ref "D52") (pin "1") (pinfunction "-_1") (pintype "passive"))
      (node (ref "U4") (pin "10") (pinfunction "OUT3_10") (pintype "output"))
    )
    (net (code "80") (name "Net-(D53--)") (class "Default")
      (node (ref "D53") (pin "1") (pinfunction "-_1") (pintype "passive"))
      (node (ref "U4") (pin "11") (pinfunction "OUT4_11") (pintype "output"))
    )
    (net (code "81") (name "Net-(D54--)") (class "Default")
      (node (ref "D54") (pin "1") (pinfunction "-_1") (pintype "passive"))
      (node (ref "U4") (pin "12") (pinfunction "OUT5_12") (pintype "output"))
    )
    (net (code "82") (name "Net-(D55--)") (class "Default")
      (node (ref "D55") (pin "1") (pinfunction "-_1") (pintype "passive"))
      (node (ref "U4") (pin "13") (pinfunction "OUT6_13") (pintype "output"))
    )
    (net (code "83") (name "Net-(D56--)") (class "Default")
      (node (ref "D56") (pin "1") (pinfunction "-_1") (pintype "passive"))
      (node (ref "U4") (pin "14") (pinfunction "OUT7_14") (pintype "output"))
    )
    (net (code "84") (name "Net-(D57--)") (class "Default")
      (node (ref "D57") (pin "1") (pinfunction "-_1") (pintype "passive"))
      (node (ref "U4") (pin "15") (pinfunction "OUT8_15") (pintype "output"))
    )
    (net (code "85") (name "Net-(D58--)") (class "Default")
      (node (ref "D58") (pin "1") (pinfunction "-_1") (pintype "passive"))
      (node (ref "U4") (pin "16") (pinfunction "OUT9_16") (pintype "output"))
    )
    (net (code "86") (name "Net-(D59--)") (class "Default")
      (node (ref "D59") (pin "1") (pinfunction "-_1") (pintype "passive"))
      (node (ref "U4") (pin "17") (pinfunction "OUT10_17") (pintype "output"))
    )
    (net (code "87") (name "Net-(D60--)") (class "Default")
      (node (ref "D60") (pin "1") (pinfunction "-_1") (pintype "passive"))
      (node (ref "U4") (pin "18") (pinfunction "OUT11_18") (pintype "output"))
    )
    (net (code "88") (name "Net-(D61--)") (class "Default")
      (node (ref "D61") (pin "1") (pinfunction "-_1") (pintype "passive"))
      (node (ref "U4") (pin "19") (pinfunction "OUT12_19") (pintype "output"))
    )
    (net (code "89") (name "Net-(D62--)") (class "Default")
      (node (ref "D62") (pin "1") (pinfunction "-_1") (pintype "passive"))
      (node (ref "U4") (pin "20") (pinfunction "OUT13_20") (pintype "output"))
    )
    (net (code "90") (name "Net-(D63--)") (class "Default")
      (node (ref "D63") (pin "1") (pinfunction "-_1") (pintype "passive"))
      (node (ref "U4") (pin "21") (pinfunction "OUT14_21") (pintype "output"))
    )
    (net (code "91") (name "Net-(D64--)") (class "Default")
      (node (ref "D64") (pin "1") (pinfunction "-_1") (pintype "passive"))
      (node (ref "U4") (pin "22") (pinfunction "OUT15_22") (pintype "output"))
    )
    (net (code "92") (name "Net-(D65-PadC)") (class "Default")
      (node (ref "D65") (pin "C") (pinfunction "C_C") (pintype "passive"))
      (node (ref "R10") (pin "2") (pinfunction "2_2") (pintype "passive"))
    )
    (net (code "93") (name "Net-(U1-SOUT)") (class "Default")
      (node (ref "U1") (pin "24") (pinfunction "SOUT_24") (pintype "output"))
      (node (ref "U2") (pin "5") (pinfunction "SIN_5") (pintype "input"))
    )
    (net (code "94") (name "Net-(U5-AREF)") (class "Default")
      (node (ref "C2") (pin "2") (pinfunction "2_2") (pintype "passive"))
      (node (ref "U5") (pin "20") (pinfunction "AREF_20") (pintype "input"))
    )
    (net (code "95") (name "Net-(U5-PB6)") (class "Default")
      (node (ref "C17") (pin "2") (pinfunction "2_2") (pintype "passive"))
      (node (ref "Q1") (pin "1") (pinfunction "1_1") (pintype "passive"))
      (node (ref "U5") (pin "7") (pinfunction "PB6_7") (pintype "bidirectional"))
    )
    (net (code "96") (name "Net-(U5-PB7)") (class "Default")
      (node (ref "C16") (pin "1") (pinfunction "1_1") (pintype "passive"))
      (node (ref "Q1") (pin "2") (pinfunction "2_2") (pintype "passive"))
      (node (ref "U5") (pin "8") (pinfunction "PB7_8") (pintype "bidirectional"))
    )
    (net (code "97") (name "RESET") (class "Default")
      (node (ref "PROG.") (pin "5") (pinfunction "P$5_5") (pintype "bidirectional"))
      (node (ref "R19") (pin "2") (pinfunction "2_2") (pintype "passive"))
      (node (ref "U5") (pin "29") (pinfunction "PC6_29") (pintype "bidirectional"))
    )
    (net (code "98") (name "RX") (class "Default")
      (node (ref "CONECTOR") (pin "7") (pinfunction "P$7_7") (pintype "bidirectional"))
      (node (ref "R9") (pin "2") (pinfunction "2_2") (pintype "passive"))
    )
    (net (code "99") (name "SIN_U2") (class "Default")
      (node (ref "U2") (pin "24") (pinfunction "SOUT_24") (pintype "output"))
      (node (ref "U3") (pin "5") (pinfunction "SIN_5") (pintype "input"))
    )
    (net (code "100") (name "SIN_U3") (class "Default")
      (node (ref "U3") (pin "24") (pinfunction "SOUT_24") (pintype "output"))
      (node (ref "U4") (pin "5") (pinfunction "SIN_5") (pintype "input"))
    )
    (net (code "101") (name "TA") (class "Default")
      (node (ref "ENC.") (pin "TA") (pinfunction "TA_TA") (pintype "bidirectional"))
      (node (ref "R11") (pin "2") (pinfunction "2_2") (pintype "passive"))
      (node (ref "R21") (pin "1") (pinfunction "1_1") (pintype "passive"))
    )
    (net (code "102") (name "TB") (class "Default")
      (node (ref "ENC.") (pin "TB") (pinfunction "TB_TB") (pintype "bidirectional"))
      (node (ref "R12") (pin "2") (pinfunction "2_2") (pintype "passive"))
      (node (ref "R22") (pin "1") (pinfunction "1_1") (pintype "passive"))
    )
    (net (code "103") (name "TX") (class "Default")
      (node (ref "CONECTOR") (pin "8") (pinfunction "P$8_8") (pintype "bidirectional"))
      (node (ref "D65") (pin "A") (pinfunction "A_A") (pintype "passive"))
    )
    (net (code "104") (name "VCC") (class "Default")
      (node (ref "C1") (pin "2") (pinfunction "2_2") (pintype "passive"))
      (node (ref "C10") (pin "+") (pinfunction "+_+") (pintype "passive"))
      (node (ref "C11") (pin "+") (pinfunction "+_+") (pintype "passive"))
      (node (ref "C12") (pin "+") (pinfunction "+_+") (pintype "passive"))
      (node (ref "C13") (pin "1") (pinfunction "1_1") (pintype "passive"))
      (node (ref "C14") (pin "1") (pinfunction "1_1") (pintype "passive"))
      (node (ref "C15") (pin "1") (pinfunction "1_1") (pintype "passive"))
      (node (ref "C18") (pin "+") (pinfunction "+_+") (pintype "passive"))
      (node (ref "C4") (pin "1") (pinfunction "1_1") (pintype "passive"))
      (node (ref "C5") (pin "1") (pinfunction "1_1") (pintype "passive"))
      (node (ref "C6") (pin "1") (pinfunction "1_1") (pintype "passive"))
      (node (ref "C7") (pin "1") (pinfunction "1_1") (pintype "passive"))
      (node (ref "C8") (pin "1") (pinfunction "1_1") (pintype "passive"))
      (node (ref "C9") (pin "+") (pinfunction "+_+") (pintype "passive"))
      (node (ref "CONECTOR") (pin "1") (pinfunction "P$1_1") (pintype "bidirectional"))
      (node (ref "CONECTOR") (pin "2") (pinfunction "P$2_2") (pintype "bidirectional"))
      (node (ref "CONECTOR") (pin "3") (pinfunction "P$3_3") (pintype "bidirectional"))
      (node (ref "D1") (pin "2") (pinfunction "+_2") (pintype "passive"))
      (node (ref "D10") (pin "2") (pinfunction "+_2") (pintype "passive"))
      (node (ref "D11") (pin "2") (pinfunction "+_2") (pintype "passive"))
      (node (ref "D12") (pin "2") (pinfunction "+_2") (pintype "passive"))
      (node (ref "D13") (pin "2") (pinfunction "+_2") (pintype "passive"))
      (node (ref "D14") (pin "2") (pinfunction "+_2") (pintype "passive"))
      (node (ref "D15") (pin "2") (pinfunction "+_2") (pintype "passive"))
      (node (ref "D16") (pin "2") (pinfunction "+_2") (pintype "passive"))
      (node (ref "D17") (pin "2") (pinfunction "+_2") (pintype "passive"))
      (node (ref "D18") (pin "2") (pinfunction "+_2") (pintype "passive"))
      (node (ref "D19") (pin "2") (pinfunction "+_2") (pintype "passive"))
      (node (ref "D2") (pin "2") (pinfunction "+_2") (pintype "passive"))
      (node (ref "D20") (pin "2") (pinfunction "+_2") (pintype "passive"))
      (node (ref "D21") (pin "2") (pinfunction "+_2") (pintype "passive"))
      (node (ref "D22") (pin "2") (pinfunction "+_2") (pintype "passive"))
      (node (ref "D23") (pin "2") (pinfunction "+_2") (pintype "passive"))
      (node (ref "D24") (pin "2") (pinfunction "+_2") (pintype "passive"))
      (node (ref "D25") (pin "2") (pinfunction "+_2") (pintype "passive"))
      (node (ref "D26") (pin "2") (pinfunction "+_2") (pintype "passive"))
      (node (ref "D27") (pin "2") (pinfunction "+_2") (pintype "passive"))
      (node (ref "D28") (pin "2") (pinfunction "+_2") (pintype "passive"))
      (node (ref "D29") (pin "2") (pinfunction "+_2") (pintype "passive"))
      (node (ref "D3") (pin "2") (pinfunction "+_2") (pintype "passive"))
      (node (ref "D30") (pin "2") (pinfunction "+_2") (pintype "passive"))
      (node (ref "D31") (pin "2") (pinfunction "+_2") (pintype "passive"))
      (node (ref "D32") (pin "2") (pinfunction "+_2") (pintype "passive"))
      (node (ref "D33") (pin "2") (pinfunction "+_2") (pintype "passive"))
      (node (ref "D34") (pin "2") (pinfunction "+_2") (pintype "passive"))
      (node (ref "D35") (pin "2") (pinfunction "+_2") (pintype "passive"))
      (node (ref "D36") (pin "2") (pinfunction "+_2") (pintype "passive"))
      (node (ref "D37") (pin "2") (pinfunction "+_2") (pintype "passive"))
      (node (ref "D38") (pin "2") (pinfunction "+_2") (pintype "passive"))
      (node (ref "D39") (pin "2") (pinfunction "+_2") (pintype "passive"))
      (node (ref "D4") (pin "2") (pinfunction "+_2") (pintype "passive"))
      (node (ref "D40") (pin "2") (pinfunction "+_2") (pintype "passive"))
      (node (ref "D41") (pin "2") (pinfunction "+_2") (pintype "passive"))
      (node (ref "D42") (pin "2") (pinfunction "+_2") (pintype "passive"))
      (node (ref "D43") (pin "2") (pinfunction "+_2") (pintype "passive"))
      (node (ref "D44") (pin "2") (pinfunction "+_2") (pintype "passive"))
      (node (ref "D45") (pin "2") (pinfunction "+_2") (pintype "passive"))
      (node (ref "D46") (pin "2") (pinfunction "+_2") (pintype "passive"))
      (node (ref "D47") (pin "2") (pinfunction "+_2") (pintype "passive"))
      (node (ref "D48") (pin "2") (pinfunction "+_2") (pintype "passive"))
      (node (ref "D49") (pin "2") (pinfunction "+_2") (pintype "passive"))
      (node (ref "D5") (pin "2") (pinfunction "+_2") (pintype "passive"))
      (node (ref "D50") (pin "2") (pinfunction "+_2") (pintype "passive"))
      (node (ref "D51") (pin "2") (pinfunction "+_2") (pintype "passive"))
      (node (ref "D52") (pin "2") (pinfunction "+_2") (pintype "passive"))
      (node (ref "D53") (pin "2") (pinfunction "+_2") (pintype "passive"))
      (node (ref "D54") (pin "2") (pinfunction "+_2") (pintype "passive"))
      (node (ref "D55") (pin "2") (pinfunction "+_2") (pintype "passive"))
      (node (ref "D56") (pin "2") (pinfunction "+_2") (pintype "passive"))
      (node (ref "D57") (pin "2") (pinfunction "+_2") (pintype "passive"))
      (node (ref "D58") (pin "2") (pinfunction "+_2") (pintype "passive"))
      (node (ref "D59") (pin "2") (pinfunction "+_2") (pintype "passive"))
      (node (ref "D6") (pin "2") (pinfunction "+_2") (pintype "passive"))
      (node (ref "D60") (pin "2") (pinfunction "+_2") (pintype "passive"))
      (node (ref "D61") (pin "2") (pinfunction "+_2") (pintype "passive"))
      (node (ref "D62") (pin "2") (pinfunction "+_2") (pintype "passive"))
      (node (ref "D63") (pin "2") (pinfunction "+_2") (pintype "passive"))
      (node (ref "D64") (pin "2") (pinfunction "+_2") (pintype "passive"))
      (node (ref "D7") (pin "2") (pinfunction "+_2") (pintype "passive"))
      (node (ref "D8") (pin "2") (pinfunction "+_2") (pintype "passive"))
      (node (ref "D9") (pin "2") (pinfunction "+_2") (pintype "passive"))
      (node (ref "PROG.") (pin "2") (pinfunction "P$2_2") (pintype "bidirectional"))
      (node (ref "R11") (pin "1") (pinfunction "1_1") (pintype "passive"))
      (node (ref "R12") (pin "1") (pinfunction "1_1") (pintype "passive"))
      (node (ref "R13") (pin "1") (pinfunction "1_1") (pintype "passive"))
      (node (ref "R14") (pin "1") (pinfunction "1_1") (pintype "passive"))
      (node (ref "R15") (pin "1") (pinfunction "1_1") (pintype "passive"))
      (node (ref "R16") (pin "1") (pinfunction "1_1") (pintype "passive"))
      (node (ref "R17") (pin "1") (pinfunction "1_1") (pintype "passive"))
      (node (ref "R19") (pin "1") (pinfunction "1_1") (pintype "passive"))
      (node (ref "R20") (pin "1") (pinfunction "1_1") (pintype "passive"))
      (node (ref "U1") (pin "26") (pinfunction "TEST_26") (pintype "input"))
      (node (ref "U1") (pin "28") (pinfunction "VCC_28") (pintype "power_in"))
      (node (ref "U2") (pin "26") (pinfunction "TEST_26") (pintype "input"))
      (node (ref "U2") (pin "28") (pinfunction "VCC_28") (pintype "power_in"))
      (node (ref "U3") (pin "26") (pinfunction "TEST_26") (pintype "input"))
      (node (ref "U3") (pin "28") (pinfunction "VCC_28") (pintype "power_in"))
      (node (ref "U4") (pin "26") (pinfunction "TEST_26") (pintype "input"))
      (node (ref "U4") (pin "28") (pinfunction "VCC_28") (pintype "power_in"))
      (node (ref "U5") (pin "18") (pinfunction "AVCC_18") (pintype "power_in"))
      (node (ref "U5") (pin "4") (pinfunction "VCC_2_4") (pintype "power_in"))
      (node (ref "U5") (pin "6") (pinfunction "VCC_6") (pintype "power_in"))
    )
    (net (code "105") (name "unconnected-(CONECTOR-P$4-Pad4)") (class "Default")
      (node (ref "CONECTOR") (pin "4") (pinfunction "P$4_4") (pintype "bidirectional"))
    )
    (net (code "106") (name "unconnected-(U1-PadTHERMAL)") (class "Default")
      (node (ref "U1") (pin "THERMAL") (pinfunction "THERMAL_THERMAL") (pintype "passive"))
    )
    (net (code "107") (name "unconnected-(U1-XERR-Pad23)") (class "Default")
      (node (ref "U1") (pin "23") (pinfunction "XERR_23") (pintype "output"))
    )
    (net (code "108") (name "unconnected-(U2-PadTHERMAL)") (class "Default")
      (node (ref "U2") (pin "THERMAL") (pinfunction "THERMAL_THERMAL") (pintype "passive"))
    )
    (net (code "109") (name "unconnected-(U2-XERR-Pad23)") (class "Default")
      (node (ref "U2") (pin "23") (pinfunction "XERR_23") (pintype "output"))
    )
    (net (code "110") (name "unconnected-(U3-PadTHERMAL)") (class "Default")
      (node (ref "U3") (pin "THERMAL") (pinfunction "THERMAL_THERMAL") (pintype "passive"))
    )
    (net (code "111") (name "unconnected-(U3-XERR-Pad23)") (class "Default")
      (node (ref "U3") (pin "23") (pinfunction "XERR_23") (pintype "output"))
    )
    (net (code "112") (name "unconnected-(U4-PadTHERMAL)") (class "Default")
      (node (ref "U4") (pin "THERMAL") (pinfunction "THERMAL_THERMAL") (pintype "passive"))
    )
    (net (code "113") (name "unconnected-(U4-SOUT-Pad24)") (class "Default")
      (node (ref "U4") (pin "24") (pinfunction "SOUT_24") (pintype "output"))
    )
    (net (code "114") (name "unconnected-(U4-XERR-Pad23)") (class "Default")
      (node (ref "U4") (pin "23") (pinfunction "XERR_23") (pintype "output"))
    )
  )
)
